# Adafruit_MPL115A2_Breakout.net
KiCad netlist of a schematic drawn in EAGLE
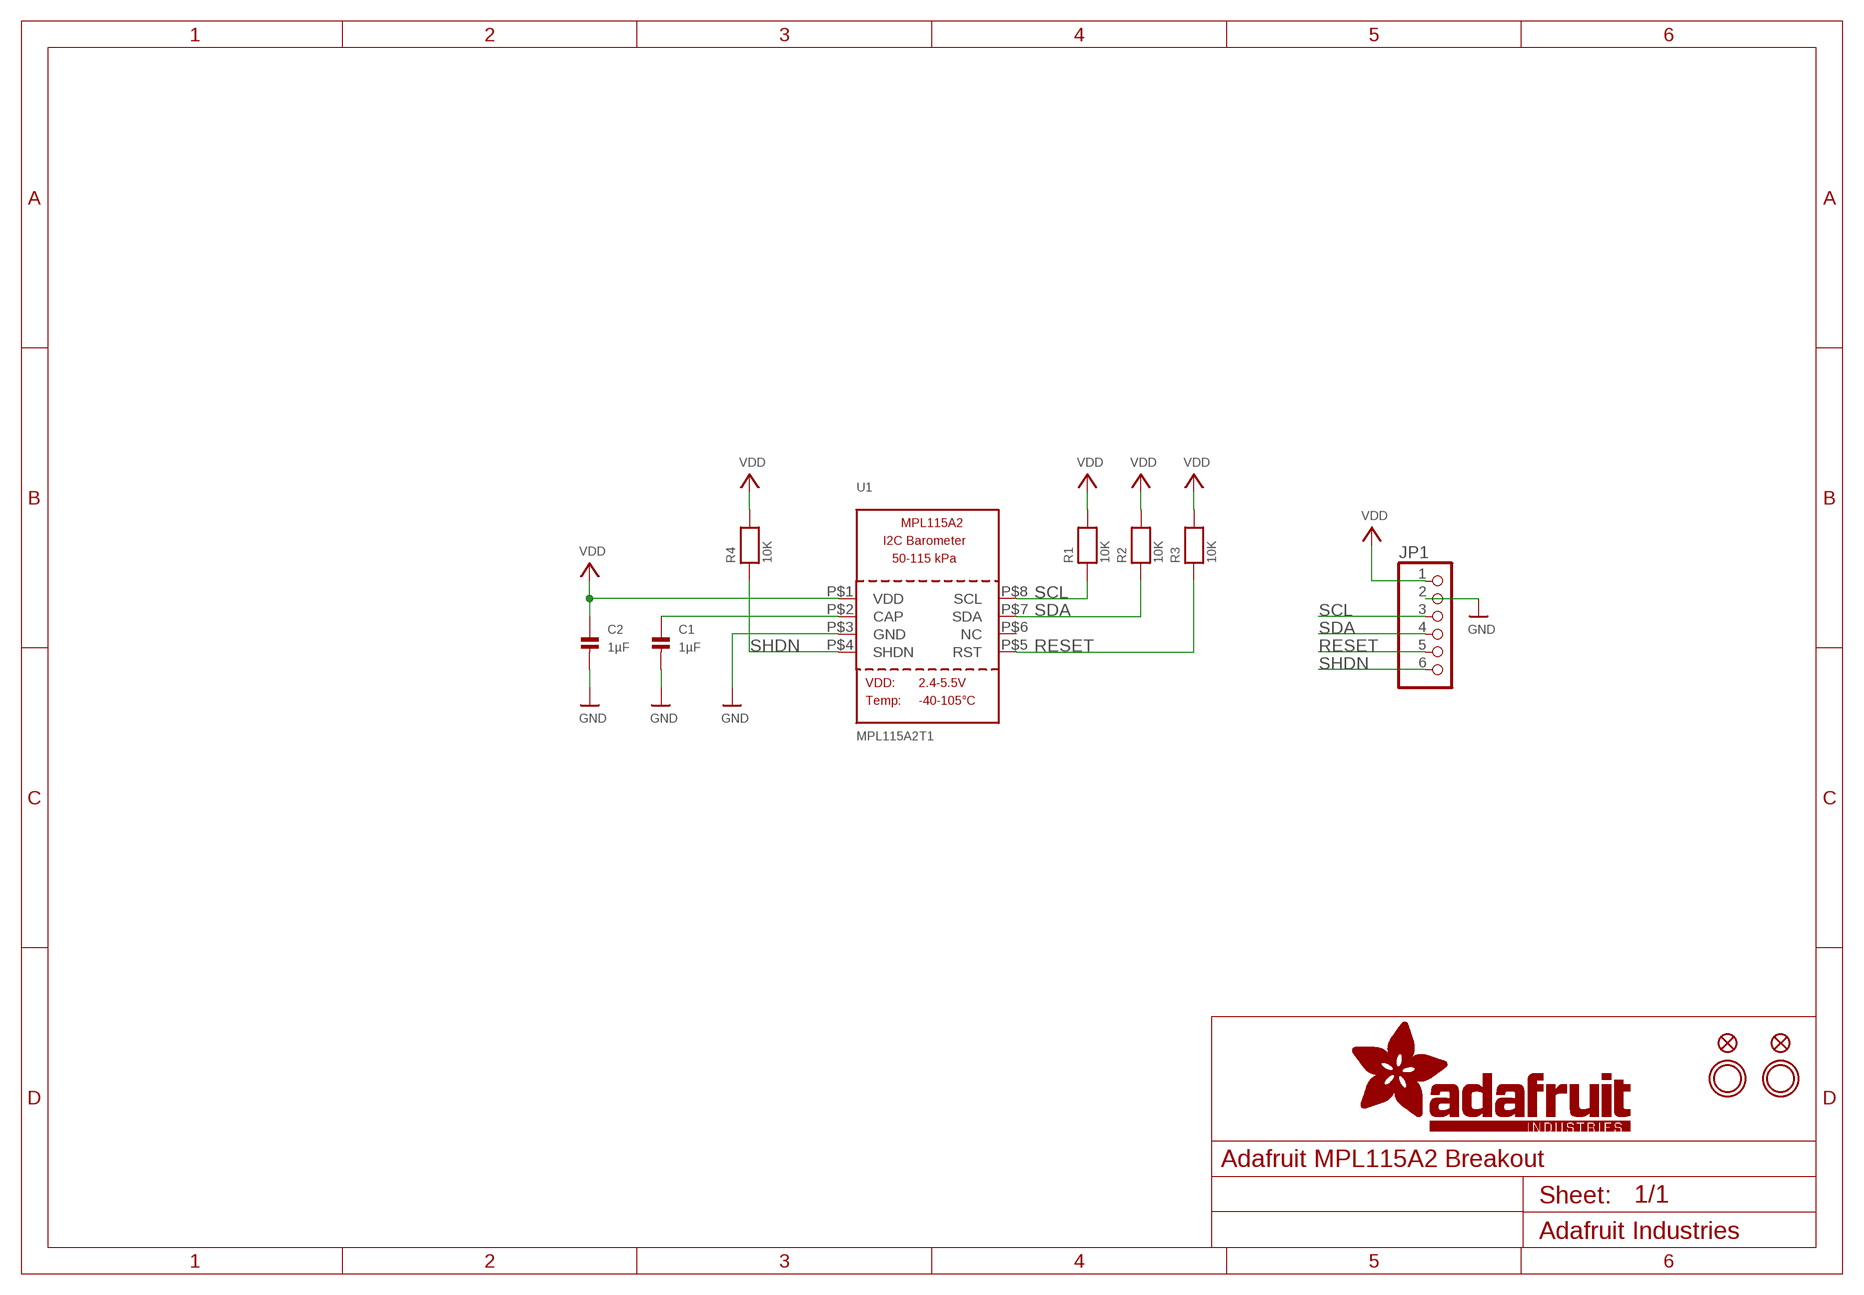
[diagram p0: schematic, sheet 1]

(export (version "E")
  (design (tool "Eeschema 10.0.6"))
  (components
    (comp (ref "C1")
      (value "1µF")
      (footprint "eagle-import:0805")
      (libsource (lib "eagle-import") (part "CAP_CERAMIC0805"))
    )
    (comp (ref "C2")
      (value "1µF")
      (footprint "eagle-import:0805")
      (libsource (lib "eagle-import") (part "CAP_CERAMIC0805"))
    )
    (comp (ref "FID1")
      (value "FIDUCIAL\"\"")
      (footprint "eagle-import:FIDUCIAL_1MM")
      (libsource (lib "eagle-import") (part "FIDUCIAL{dblquote}{dblquote}"))
    )
    (comp (ref "FID2")
      (value "FIDUCIAL\"\"")
      (footprint "eagle-import:FIDUCIAL_1MM")
      (libsource (lib "eagle-import") (part "FIDUCIAL{dblquote}{dblquote}"))
    )
    (comp (ref "JP1")
      (value "HEADER-1X670MIL")
      (footprint "eagle-import:1X06_ROUND_70")
      (libsource (lib "eagle-import") (part "HEADER-1X670MIL"))
    )
    (comp (ref "R1")
      (value "10K")
      (footprint "eagle-import:0805")
      (libsource (lib "eagle-import") (part "RESISTOR0805"))
    )
    (comp (ref "R2")
      (value "10K")
      (footprint "eagle-import:0805")
      (libsource (lib "eagle-import") (part "RESISTOR0805"))
    )
    (comp (ref "R3")
      (value "10K")
      (footprint "eagle-import:0805")
      (libsource (lib "eagle-import") (part "RESISTOR0805"))
    )
    (comp (ref "R4")
      (value "10K")
      (footprint "eagle-import:0805")
      (libsource (lib "eagle-import") (part "RESISTOR0805"))
    )
    (comp (ref "U$8")
      (value "MOUNTINGHOLE2.5")
      (footprint "eagle-import:MOUNTINGHOLE_2.5_PLATED")
      (libsource (lib "eagle-import") (part "MOUNTINGHOLE2.5"))
    )
    (comp (ref "U$9")
      (value "MOUNTINGHOLE2.5")
      (footprint "eagle-import:MOUNTINGHOLE_2.5_PLATED")
      (libsource (lib "eagle-import") (part "MOUNTINGHOLE2.5"))
    )
    (comp (ref "U1")
      (value "MPL115A2T1")
      (footprint "eagle-import:LGA8")
      (libsource (lib "eagle-import") (part "MPL115A2"))
    )
  )
  (nets
    (net (code "1") (name "/RESET") (class "Default")
      (node (ref "JP1") (pin "5") (pinfunction "5_5") (pintype "passive"))
      (node (ref "R3") (pin "1") (pinfunction "1_1") (pintype "passive"))
      (node (ref "U1") (pin "P$5") (pinfunction "RST_P$5") (pintype "bidirectional"))
    )
    (net (code "2") (name "/SCL") (class "Default")
      (node (ref "JP1") (pin "3") (pinfunction "3_3") (pintype "passive"))
      (node (ref "R1") (pin "1") (pinfunction "1_1") (pintype "passive"))
      (node (ref "U1") (pin "P$8") (pinfunction "SCL_P$8") (pintype "bidirectional"))
    )
    (net (code "3") (name "/SDA") (class "Default")
      (node (ref "JP1") (pin "4") (pinfunction "4_4") (pintype "passive"))
      (node (ref "R2") (pin "1") (pinfunction "1_1") (pintype "passive"))
      (node (ref "U1") (pin "P$7") (pinfunction "SDA_P$7") (pintype "bidirectional"))
    )
    (net (code "4") (name "/SHDN") (class "Default")
      (node (ref "JP1") (pin "6") (pinfunction "6_6") (pintype "passive"))
      (node (ref "R4") (pin "1") (pinfunction "1_1") (pintype "passive"))
      (node (ref "U1") (pin "P$4") (pinfunction "SHDN_P$4") (pintype "bidirectional"))
    )
    (net (code "5") (name "GND") (class "Default")
      (node (ref "C1") (pin "2") (pinfunction "P$2_2") (pintype "passive"))
      (node (ref "C2") (pin "2") (pinfunction "P$2_2") (pintype "passive"))
      (node (ref "JP1") (pin "2") (pinfunction "2_2") (pintype "passive"))
      (node (ref "U1") (pin "P$3") (pinfunction "GND_P$3") (pintype "power_in"))
    )
    (net (code "6") (name "Net-(C1-P$1)") (class "Default")
      (node (ref "C1") (pin "1") (pinfunction "P$1_1") (pintype "passive"))
      (node (ref "U1") (pin "P$2") (pinfunction "CAP_P$2") (pintype "bidirectional"))
    )
    (net (code "7") (name "VDD") (class "Default")
      (node (ref "C2") (pin "1") (pinfunction "P$1_1") (pintype "passive"))
      (node (ref "JP1") (pin "1") (pinfunction "1_1") (pintype "passive"))
      (node (ref "R1") (pin "2") (pinfunction "2_2") (pintype "passive"))
      (node (ref "R2") (pin "2") (pinfunction "2_2") (pintype "passive"))
      (node (ref "R3") (pin "2") (pinfunction "2_2") (pintype "passive"))
      (node (ref "R4") (pin "2") (pinfunction "2_2") (pintype "passive"))
      (node (ref "U1") (pin "P$1") (pinfunction "VDD_P$1") (pintype "power_in"))
    )
    (net (code "8") (name "unconnected-(U1-NC-PadP$6)") (class "Default")
      (node (ref "U1") (pin "P$6") (pinfunction "NC_P$6") (pintype "no_connect"))
    )
  )
)
